# FPGA_BANK_B.net
KiCad netlist of a schematic drawn in Altium Designer
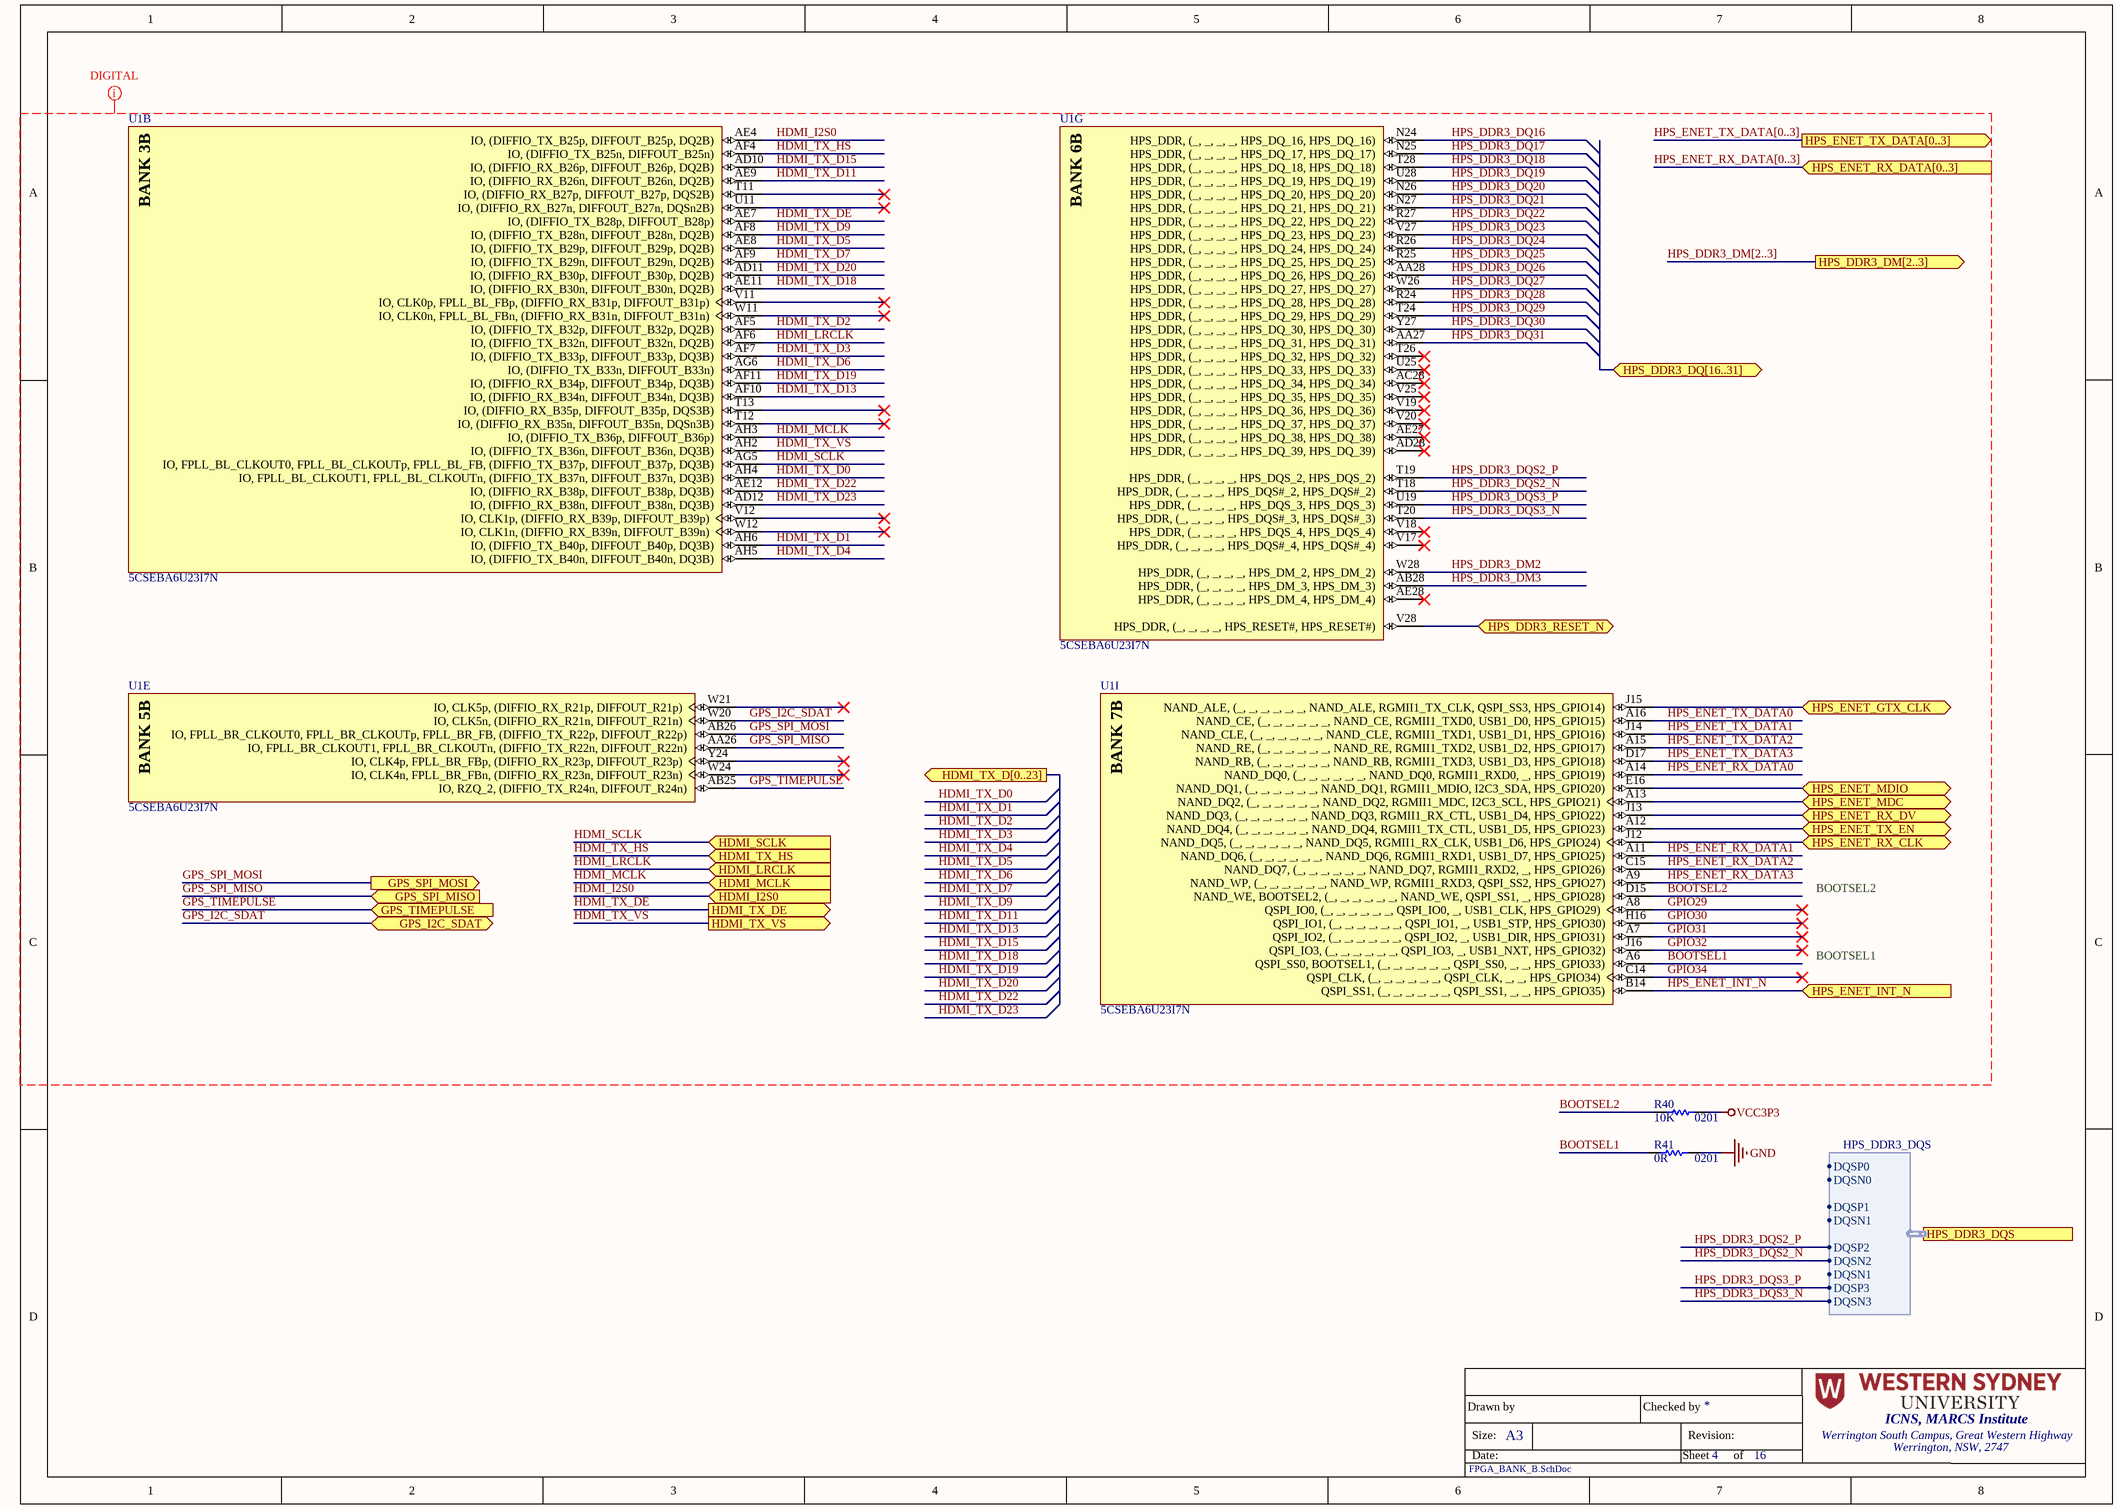
[diagram p0: FPGA_BANK_B.SchDoc]

(export (version "E")
  (design (tool "Eeschema 10.0.6"))
  (components
    (comp (ref "R40")
      (value "10K")
      (footprint "RES 0201 (0603)")
      (description "Res Thick Film 0201 10K Ohm 1% 0.05W(1/20W) ±200ppm/C Pad SMD Automotive T/R")
      (fields
        (field (name "MANUFACTURER") "Yageo")
        (field (name "MANUFACTURER PART NUMBER") "AC0201FR-0710KL")
        (field (name "CASE CODE (IMPERIAL)") "0201")
        (field (name "SOURCE") "ICNS_PropheseeLib.SchLib")
      )
      (libsource (lib "Western Sydney University - ICNS") (part "Symbol"))
    )
    (comp (ref "R41")
      (value "0R")
      (footprint "RES 0201 (0603)")
      (description "Res Thick Film 0201 0 Ohm Sulfur Resistant Pad SMD Automotive T/R")
      (fields
        (field (name "MANUFACTURER") "Yageo")
        (field (name "MANUFACTURER PART NUMBER") "AF0201JR-070RL")
        (field (name "CASE CODE (IMPERIAL)") "0201")
        (field (name "SOURCE") "ICNS_PropheseeLib.SchLib")
      )
      (libsource (lib "Western Sydney University - ICNS") (part "Symbol"))
    )
    (comp (ref "U1")
      (value "5CSEBA6U23I7N")
      (footprint "ALTR-UBGA672_A-185")
      (fields (field (name "MANUFACTURER") "Altera") (field (name "SOURCE") "ICNS_PropheseeLib.SchLib"))
      (libsource (lib "Western Sydney University - ICNS") (part "5CSEBA6U23I7N"))
    )
  )
  (nets
    (net (code "9") (name "/BOOTSEL1") (class "Default")
      (node (ref "R41") (pin "1") (pinfunction "1_1") (pintype "passive"))
      (node (ref "U1") (pin "A6") (pinfunction "QSPI_SS0,_BOOTSEL1,_(_,__,__,__,__,__,_QSPI_SS0,__,__,_HPS_GPIO33)_A6") (pintype "bidirectional"))
    )
    (net (code "10") (name "/BOOTSEL2") (class "Default")
      (node (ref "R40") (pin "2") (pinfunction "2_2") (pintype "passive"))
      (node (ref "U1") (pin "D15") (pinfunction "NAND_WE,_BOOTSEL2,_(_,__,__,__,__,__,_NAND_WE,_QSPI_SS1,__,_HPS_GPIO28)_D15") (pintype "bidirectional"))
    )
    (net (code "11") (name "/GPIO29") (class "Default")
      (node (ref "U1") (pin "A8") (pinfunction "QSPI_IO0,_(_,__,__,__,__,__,_QSPI_IO0,__,_USB1_CLK,_HPS_GPIO29)_A8") (pintype "bidirectional+no_connect"))
    )
    (net (code "12") (name "/GPIO30") (class "Default")
      (node (ref "U1") (pin "H16") (pinfunction "QSPI_IO1,_(_,__,__,__,__,__,_QSPI_IO1,__,_USB1_STP,_HPS_GPIO30)_H16") (pintype "bidirectional+no_connect"))
    )
    (net (code "13") (name "/GPIO31") (class "Default")
      (node (ref "U1") (pin "A7") (pinfunction "QSPI_IO2,_(_,__,__,__,__,__,_QSPI_IO2,__,_USB1_DIR,_HPS_GPIO31)_A7") (pintype "bidirectional+no_connect"))
    )
    (net (code "14") (name "/GPIO32") (class "Default")
      (node (ref "U1") (pin "J16") (pinfunction "QSPI_IO3,_(_,__,__,__,__,__,_QSPI_IO3,__,_USB1_NXT,_HPS_GPIO32)_J16") (pintype "bidirectional+no_connect"))
    )
    (net (code "15") (name "/GPIO34") (class "Default")
      (node (ref "U1") (pin "C14") (pinfunction "QSPI_CLK,_(_,__,__,__,__,__,_QSPI_CLK,__,__,_HPS_GPIO34)_C14") (pintype "bidirectional+no_connect"))
    )
    (net (code "16") (name "/GPS_I2C_SDAT") (class "Default")
      (node (ref "U1") (pin "W20") (pinfunction "IO,_CLK5n,_(DIFFIO_RX_R21n,_DIFFOUT_R21n)_W20") (pintype "bidirectional"))
    )
    (net (code "17") (name "/GPS_SPI_MISO") (class "Default")
      (node (ref "U1") (pin "AA26") (pinfunction "IO,_FPLL_BR_CLKOUT1,_FPLL_BR_CLKOUTn,_(DIFFIO_TX_R22n,_DIFFOUT_R22n)_AA26") (pintype "bidirectional"))
    )
    (net (code "18") (name "/GPS_SPI_MOSI") (class "Default")
      (node (ref "U1") (pin "AB26") (pinfunction "IO,_FPLL_BR_CLKOUT0,_FPLL_BR_CLKOUTp,_FPLL_BR_FB,_(DIFFIO_TX_R22p,_DIFFOUT_R22p)_AB26") (pintype "bidirectional"))
    )
    (net (code "19") (name "/GPS_TIMEPULSE") (class "Default")
      (node (ref "U1") (pin "AB25") (pinfunction "IO,_RZQ_2,_(DIFFIO_TX_R24n,_DIFFOUT_R24n)_AB25") (pintype "bidirectional"))
    )
    (net (code "20") (name "/HDMI_I2S0") (class "Default")
      (node (ref "U1") (pin "AE4") (pinfunction "IO,_(DIFFIO_TX_B25p,_DIFFOUT_B25p,_DQ2B)_AE4") (pintype "bidirectional"))
    )
    (net (code "21") (name "/HDMI_LRCLK") (class "Default")
      (node (ref "U1") (pin "AF6") (pinfunction "IO,_(DIFFIO_TX_B32n,_DIFFOUT_B32n,_DQ2B)_AF6") (pintype "bidirectional"))
    )
    (net (code "22") (name "/HDMI_MCLK") (class "Default")
      (node (ref "U1") (pin "AH3") (pinfunction "IO,_(DIFFIO_TX_B36p,_DIFFOUT_B36p)_AH3") (pintype "bidirectional"))
    )
    (net (code "23") (name "/HDMI_SCLK") (class "Default")
      (node (ref "U1") (pin "AG5") (pinfunction "IO,_FPLL_BL_CLKOUT0,_FPLL_BL_CLKOUTp,_FPLL_BL_FB,_(DIFFIO_TX_B37p,_DIFFOUT_B37p,_DQ3B)_AG5") (pintype "bidirectional"))
    )
    (net (code "24") (name "/HDMI_TX_D0") (class "Default")
      (node (ref "U1") (pin "AH4") (pinfunction "IO,_FPLL_BL_CLKOUT1,_FPLL_BL_CLKOUTn,_(DIFFIO_TX_B37n,_DIFFOUT_B37n,_DQ3B)_AH4") (pintype "bidirectional"))
    )
    (net (code "25") (name "/HDMI_TX_D1") (class "Default")
      (node (ref "U1") (pin "AH6") (pinfunction "IO,_(DIFFIO_TX_B40p,_DIFFOUT_B40p,_DQ3B)_AH6") (pintype "bidirectional"))
    )
    (net (code "26") (name "/HDMI_TX_D2") (class "Default")
      (node (ref "U1") (pin "AF5") (pinfunction "IO,_(DIFFIO_TX_B32p,_DIFFOUT_B32p,_DQ2B)_AF5") (pintype "bidirectional"))
    )
    (net (code "27") (name "/HDMI_TX_D3") (class "Default")
      (node (ref "U1") (pin "AF7") (pinfunction "IO,_(DIFFIO_TX_B33p,_DIFFOUT_B33p,_DQ3B)_AF7") (pintype "bidirectional"))
    )
    (net (code "28") (name "/HDMI_TX_D4") (class "Default")
      (node (ref "U1") (pin "AH5") (pinfunction "IO,_(DIFFIO_TX_B40n,_DIFFOUT_B40n,_DQ3B)_AH5") (pintype "bidirectional"))
    )
    (net (code "29") (name "/HDMI_TX_D5") (class "Default")
      (node (ref "U1") (pin "AE8") (pinfunction "IO,_(DIFFIO_TX_B29p,_DIFFOUT_B29p,_DQ2B)_AE8") (pintype "bidirectional"))
    )
    (net (code "30") (name "/HDMI_TX_D6") (class "Default")
      (node (ref "U1") (pin "AG6") (pinfunction "IO,_(DIFFIO_TX_B33n,_DIFFOUT_B33n)_AG6") (pintype "bidirectional"))
    )
    (net (code "31") (name "/HDMI_TX_D7") (class "Default")
      (node (ref "U1") (pin "AF9") (pinfunction "IO,_(DIFFIO_TX_B29n,_DIFFOUT_B29n,_DQ2B)_AF9") (pintype "bidirectional"))
    )
    (net (code "32") (name "/HDMI_TX_D9") (class "Default")
      (node (ref "U1") (pin "AF8") (pinfunction "IO,_(DIFFIO_TX_B28n,_DIFFOUT_B28n,_DQ2B)_AF8") (pintype "bidirectional"))
    )
    (net (code "33") (name "/HDMI_TX_D11") (class "Default")
      (node (ref "U1") (pin "AE9") (pinfunction "IO,_(DIFFIO_RX_B26n,_DIFFOUT_B26n,_DQ2B)_AE9") (pintype "bidirectional"))
    )
    (net (code "34") (name "/HDMI_TX_D13") (class "Default")
      (node (ref "U1") (pin "AF10") (pinfunction "IO,_(DIFFIO_RX_B34n,_DIFFOUT_B34n,_DQ3B)_AF10") (pintype "bidirectional"))
    )
    (net (code "35") (name "/HDMI_TX_D15") (class "Default")
      (node (ref "U1") (pin "AD10") (pinfunction "IO,_(DIFFIO_RX_B26p,_DIFFOUT_B26p,_DQ2B)_AD10") (pintype "bidirectional"))
    )
    (net (code "36") (name "/HDMI_TX_D18") (class "Default")
      (node (ref "U1") (pin "AE11") (pinfunction "IO,_(DIFFIO_RX_B30n,_DIFFOUT_B30n,_DQ2B)_AE11") (pintype "bidirectional"))
    )
    (net (code "37") (name "/HDMI_TX_D19") (class "Default")
      (node (ref "U1") (pin "AF11") (pinfunction "IO,_(DIFFIO_RX_B34p,_DIFFOUT_B34p,_DQ3B)_AF11") (pintype "bidirectional"))
    )
    (net (code "38") (name "/HDMI_TX_D20") (class "Default")
      (node (ref "U1") (pin "AD11") (pinfunction "IO,_(DIFFIO_RX_B30p,_DIFFOUT_B30p,_DQ2B)_AD11") (pintype "bidirectional"))
    )
    (net (code "39") (name "/HDMI_TX_D22") (class "Default")
      (node (ref "U1") (pin "AE12") (pinfunction "IO,_(DIFFIO_RX_B38p,_DIFFOUT_B38p,_DQ3B)_AE12") (pintype "bidirectional"))
    )
    (net (code "40") (name "/HDMI_TX_D23") (class "Default")
      (node (ref "U1") (pin "AD12") (pinfunction "IO,_(DIFFIO_RX_B38n,_DIFFOUT_B38n,_DQ3B)_AD12") (pintype "bidirectional"))
    )
    (net (code "41") (name "/HDMI_TX_DE") (class "Default")
      (node (ref "U1") (pin "AE7") (pinfunction "IO,_(DIFFIO_TX_B28p,_DIFFOUT_B28p)_AE7") (pintype "bidirectional"))
    )
    (net (code "43") (name "/HDMI_TX_HS") (class "Default")
      (node (ref "U1") (pin "AF4") (pinfunction "IO,_(DIFFIO_TX_B25n,_DIFFOUT_B25n)_AF4") (pintype "bidirectional"))
    )
    (net (code "44") (name "/HDMI_TX_VS") (class "Default")
      (node (ref "U1") (pin "AH2") (pinfunction "IO,_(DIFFIO_TX_B36n,_DIFFOUT_B36n,_DQ3B)_AH2") (pintype "bidirectional"))
    )
    (net (code "45") (name "/HPS_DDR3_DM2") (class "Default")
      (node (ref "U1") (pin "W28") (pinfunction "HPS_DDR,_(_,__,__,__,_HPS_DM_2,_HPS_DM_2)_W28") (pintype "bidirectional"))
    )
    (net (code "46") (name "/HPS_DDR3_DM3") (class "Default")
      (node (ref "U1") (pin "AB28") (pinfunction "HPS_DDR,_(_,__,__,__,_HPS_DM_3,_HPS_DM_3)_AB28") (pintype "bidirectional"))
    )
    (net (code "48") (name "/HPS_DDR3_DQ16") (class "Default")
      (node (ref "U1") (pin "N24") (pinfunction "HPS_DDR,_(_,__,__,__,_HPS_DQ_16,_HPS_DQ_16)_N24") (pintype "bidirectional"))
    )
    (net (code "49") (name "/HPS_DDR3_DQ17") (class "Default")
      (node (ref "U1") (pin "N25") (pinfunction "HPS_DDR,_(_,__,__,__,_HPS_DQ_17,_HPS_DQ_17)_N25") (pintype "bidirectional"))
    )
    (net (code "50") (name "/HPS_DDR3_DQ18") (class "Default")
      (node (ref "U1") (pin "T28") (pinfunction "HPS_DDR,_(_,__,__,__,_HPS_DQ_18,_HPS_DQ_18)_T28") (pintype "bidirectional"))
    )
    (net (code "51") (name "/HPS_DDR3_DQ19") (class "Default")
      (node (ref "U1") (pin "U28") (pinfunction "HPS_DDR,_(_,__,__,__,_HPS_DQ_19,_HPS_DQ_19)_U28") (pintype "bidirectional"))
    )
    (net (code "52") (name "/HPS_DDR3_DQ20") (class "Default")
      (node (ref "U1") (pin "N26") (pinfunction "HPS_DDR,_(_,__,__,__,_HPS_DQ_20,_HPS_DQ_20)_N26") (pintype "bidirectional"))
    )
    (net (code "53") (name "/HPS_DDR3_DQ21") (class "Default")
      (node (ref "U1") (pin "N27") (pinfunction "HPS_DDR,_(_,__,__,__,_HPS_DQ_21,_HPS_DQ_21)_N27") (pintype "bidirectional"))
    )
    (net (code "54") (name "/HPS_DDR3_DQ22") (class "Default")
      (node (ref "U1") (pin "R27") (pinfunction "HPS_DDR,_(_,__,__,__,_HPS_DQ_22,_HPS_DQ_22)_R27") (pintype "bidirectional"))
    )
    (net (code "55") (name "/HPS_DDR3_DQ23") (class "Default")
      (node (ref "U1") (pin "V27") (pinfunction "HPS_DDR,_(_,__,__,__,_HPS_DQ_23,_HPS_DQ_23)_V27") (pintype "bidirectional"))
    )
    (net (code "56") (name "/HPS_DDR3_DQ24") (class "Default")
      (node (ref "U1") (pin "R26") (pinfunction "HPS_DDR,_(_,__,__,__,_HPS_DQ_24,_HPS_DQ_24)_R26") (pintype "bidirectional"))
    )
    (net (code "57") (name "/HPS_DDR3_DQ25") (class "Default")
      (node (ref "U1") (pin "R25") (pinfunction "HPS_DDR,_(_,__,__,__,_HPS_DQ_25,_HPS_DQ_25)_R25") (pintype "bidirectional"))
    )
    (net (code "58") (name "/HPS_DDR3_DQ26") (class "Default")
      (node (ref "U1") (pin "AA28") (pinfunction "HPS_DDR,_(_,__,__,__,_HPS_DQ_26,_HPS_DQ_26)_AA28") (pintype "bidirectional"))
    )
    (net (code "59") (name "/HPS_DDR3_DQ27") (class "Default")
      (node (ref "U1") (pin "W26") (pinfunction "HPS_DDR,_(_,__,__,__,_HPS_DQ_27,_HPS_DQ_27)_W26") (pintype "bidirectional"))
    )
    (net (code "60") (name "/HPS_DDR3_DQ28") (class "Default")
      (node (ref "U1") (pin "R24") (pinfunction "HPS_DDR,_(_,__,__,__,_HPS_DQ_28,_HPS_DQ_28)_R24") (pintype "bidirectional"))
    )
    (net (code "61") (name "/HPS_DDR3_DQ29") (class "Default")
      (node (ref "U1") (pin "T24") (pinfunction "HPS_DDR,_(_,__,__,__,_HPS_DQ_29,_HPS_DQ_29)_T24") (pintype "bidirectional"))
    )
    (net (code "62") (name "/HPS_DDR3_DQ30") (class "Default")
      (node (ref "U1") (pin "Y27") (pinfunction "HPS_DDR,_(_,__,__,__,_HPS_DQ_30,_HPS_DQ_30)_Y27") (pintype "bidirectional"))
    )
    (net (code "63") (name "/HPS_DDR3_DQ31") (class "Default")
      (node (ref "U1") (pin "AA27") (pinfunction "HPS_DDR,_(_,__,__,__,_HPS_DQ_31,_HPS_DQ_31)_AA27") (pintype "bidirectional"))
    )
    (net (code "64") (name "/HPS_DDR3_DQS2_N") (class "Default")
      (node (ref "U1") (pin "T18") (pinfunction "HPS_DDR,_(_,__,__,__,_HPS_DQS#_2,_HPS_DQS#_2)_T18") (pintype "bidirectional"))
    )
    (net (code "65") (name "/HPS_DDR3_DQS2_P") (class "Default")
      (node (ref "U1") (pin "T19") (pinfunction "HPS_DDR,_(_,__,__,__,_HPS_DQS_2,_HPS_DQS_2)_T19") (pintype "bidirectional"))
    )
    (net (code "66") (name "/HPS_DDR3_DQS3_N") (class "Default")
      (node (ref "U1") (pin "T20") (pinfunction "HPS_DDR,_(_,__,__,__,_HPS_DQS#_3,_HPS_DQS#_3)_T20") (pintype "bidirectional"))
    )
    (net (code "67") (name "/HPS_DDR3_DQS3_P") (class "Default")
      (node (ref "U1") (pin "U19") (pinfunction "HPS_DDR,_(_,__,__,__,_HPS_DQS_3,_HPS_DQS_3)_U19") (pintype "bidirectional"))
    )
    (net (code "69") (name "/HPS_DDR3_RESET_N") (class "Default")
      (node (ref "U1") (pin "V28") (pinfunction "HPS_DDR,_(_,__,__,__,_HPS_RESET#,_HPS_RESET#)_V28") (pintype "bidirectional"))
    )
    (net (code "70") (name "/HPS_ENET_GTX_CLK") (class "Default")
      (node (ref "U1") (pin "J15") (pinfunction "NAND_ALE,_(_,__,__,__,__,__,_NAND_ALE,_RGMII1_TX_CLK,_QSPI_SS3,_HPS_GPIO14)_J15") (pintype "bidirectional"))
    )
    (net (code "71") (name "/HPS_ENET_INT_N") (class "Default")
      (node (ref "U1") (pin "B14") (pinfunction "QSPI_SS1,_(_,__,__,__,__,__,_QSPI_SS1,__,__,_HPS_GPIO35)_B14") (pintype "bidirectional"))
    )
    (net (code "72") (name "/HPS_ENET_MDC") (class "Default")
      (node (ref "U1") (pin "A13") (pinfunction "NAND_DQ2,_(_,__,__,__,__,__,_NAND_DQ2,_RGMII1_MDC,_I2C3_SCL,_HPS_GPIO21)_A13") (pintype "bidirectional"))
    )
    (net (code "73") (name "/HPS_ENET_MDIO") (class "Default")
      (node (ref "U1") (pin "E16") (pinfunction "NAND_DQ1,_(_,__,__,__,__,__,_NAND_DQ1,_RGMII1_MDIO,_I2C3_SDA,_HPS_GPIO20)_E16") (pintype "bidirectional"))
    )
    (net (code "74") (name "/HPS_ENET_RX_CLK") (class "Default")
      (node (ref "U1") (pin "J12") (pinfunction "NAND_DQ5,_(_,__,__,__,__,__,_NAND_DQ5,_RGMII1_RX_CLK,_USB1_D6,_HPS_GPIO24)_J12") (pintype "bidirectional"))
    )
    (net (code "75") (name "/HPS_ENET_RX_DATA0") (class "Default")
      (node (ref "U1") (pin "A14") (pinfunction "NAND_DQ0,_(_,__,__,__,__,__,_NAND_DQ0,_RGMII1_RXD0,__,_HPS_GPIO19)_A14") (pintype "bidirectional"))
    )
    (net (code "76") (name "/HPS_ENET_RX_DATA1") (class "Default")
      (node (ref "U1") (pin "A11") (pinfunction "NAND_DQ6,_(_,__,__,__,__,__,_NAND_DQ6,_RGMII1_RXD1,_USB1_D7,_HPS_GPIO25)_A11") (pintype "bidirectional"))
    )
    (net (code "77") (name "/HPS_ENET_RX_DATA2") (class "Default")
      (node (ref "U1") (pin "C15") (pinfunction "NAND_DQ7,_(_,__,__,__,__,__,_NAND_DQ7,_RGMII1_RXD2,__,_HPS_GPIO26)_C15") (pintype "bidirectional"))
    )
    (net (code "78") (name "/HPS_ENET_RX_DATA3") (class "Default")
      (node (ref "U1") (pin "A9") (pinfunction "NAND_WP,_(_,__,__,__,__,__,_NAND_WP,_RGMII1_RXD3,_QSPI_SS2,_HPS_GPIO27)_A9") (pintype "bidirectional"))
    )
    (net (code "80") (name "/HPS_ENET_RX_DV") (class "Default")
      (node (ref "U1") (pin "J13") (pinfunction "NAND_DQ3,_(_,__,__,__,__,__,_NAND_DQ3,_RGMII1_RX_CTL,_USB1_D4,_HPS_GPIO22)_J13") (pintype "bidirectional"))
    )
    (net (code "81") (name "/HPS_ENET_TX_DATA0") (class "Default")
      (node (ref "U1") (pin "A16") (pinfunction "NAND_CE,_(_,__,__,__,__,__,_NAND_CE,_RGMII1_TXD0,_USB1_D0,_HPS_GPIO15)_A16") (pintype "bidirectional"))
    )
    (net (code "82") (name "/HPS_ENET_TX_DATA1") (class "Default")
      (node (ref "U1") (pin "J14") (pinfunction "NAND_CLE,_(_,__,__,__,__,__,_NAND_CLE,_RGMII1_TXD1,_USB1_D1,_HPS_GPIO16)_J14") (pintype "bidirectional"))
    )
    (net (code "83") (name "/HPS_ENET_TX_DATA2") (class "Default")
      (node (ref "U1") (pin "A15") (pinfunction "NAND_RE,_(_,__,__,__,__,__,_NAND_RE,_RGMII1_TXD2,_USB1_D2,_HPS_GPIO17)_A15") (pintype "bidirectional"))
    )
    (net (code "84") (name "/HPS_ENET_TX_DATA3") (class "Default")
      (node (ref "U1") (pin "D17") (pinfunction "NAND_RB,_(_,__,__,__,__,__,_NAND_RB,_RGMII1_TXD3,_USB1_D3,_HPS_GPIO18)_D17") (pintype "bidirectional"))
    )
    (net (code "86") (name "/HPS_ENET_TX_EN") (class "Default")
      (node (ref "U1") (pin "A12") (pinfunction "NAND_DQ4,_(_,__,__,__,__,__,_NAND_DQ4,_RGMII1_TX_CTL,_USB1_D5,_HPS_GPIO23)_A12") (pintype "bidirectional"))
    )
    (net (code "88") (name "GND") (class "Default")
      (node (ref "R41") (pin "2") (pinfunction "2_2") (pintype "passive"))
    )
    (net (code "89") (name "VCC3P3") (class "Default")
      (node (ref "R40") (pin "1") (pinfunction "1_1") (pintype "passive"))
    )
    (net (code "90") (name "unconnected-(U1B-IO,_(DIFFIO_RX_B27n,_DIFFOUT_B27n,_DQSn2B)-PadU11)") (class "Default")
      (node (ref "U1") (pin "U11") (pinfunction "IO,_(DIFFIO_RX_B27n,_DIFFOUT_B27n,_DQSn2B)_U11") (pintype "bidirectional+no_connect"))
    )
    (net (code "91") (name "unconnected-(U1B-IO,_(DIFFIO_RX_B27p,_DIFFOUT_B27p,_DQS2B)-PadT11)") (class "Default")
      (node (ref "U1") (pin "T11") (pinfunction "IO,_(DIFFIO_RX_B27p,_DIFFOUT_B27p,_DQS2B)_T11") (pintype "bidirectional+no_connect"))
    )
    (net (code "92") (name "unconnected-(U1B-IO,_(DIFFIO_RX_B35n,_DIFFOUT_B35n,_DQSn3B)-PadT12)") (class "Default")
      (node (ref "U1") (pin "T12") (pinfunction "IO,_(DIFFIO_RX_B35n,_DIFFOUT_B35n,_DQSn3B)_T12") (pintype "bidirectional+no_connect"))
    )
    (net (code "93") (name "unconnected-(U1B-IO,_(DIFFIO_RX_B35p,_DIFFOUT_B35p,_DQS3B)-PadT13)") (class "Default")
      (node (ref "U1") (pin "T13") (pinfunction "IO,_(DIFFIO_RX_B35p,_DIFFOUT_B35p,_DQS3B)_T13") (pintype "bidirectional+no_connect"))
    )
    (net (code "94") (name "unconnected-(U1B-IO,_CLK0n,_FPLL_BL_FBn,_(DIFFIO_RX_B31n,_DIFFOUT_B31n)-PadW11)") (class "Default")
      (node (ref "U1") (pin "W11") (pinfunction "IO,_CLK0n,_FPLL_BL_FBn,_(DIFFIO_RX_B31n,_DIFFOUT_B31n)_W11") (pintype "bidirectional+no_connect"))
    )
    (net (code "95") (name "unconnected-(U1B-IO,_CLK0p,_FPLL_BL_FBp,_(DIFFIO_RX_B31p,_DIFFOUT_B31p)-PadV11)") (class "Default")
      (node (ref "U1") (pin "V11") (pinfunction "IO,_CLK0p,_FPLL_BL_FBp,_(DIFFIO_RX_B31p,_DIFFOUT_B31p)_V11") (pintype "bidirectional+no_connect"))
    )
    (net (code "96") (name "unconnected-(U1B-IO,_CLK1n,_(DIFFIO_RX_B39n,_DIFFOUT_B39n)-PadW12)") (class "Default")
      (node (ref "U1") (pin "W12") (pinfunction "IO,_CLK1n,_(DIFFIO_RX_B39n,_DIFFOUT_B39n)_W12") (pintype "bidirectional+no_connect"))
    )
    (net (code "97") (name "unconnected-(U1B-IO,_CLK1p,_(DIFFIO_RX_B39p,_DIFFOUT_B39p)-PadV12)") (class "Default")
      (node (ref "U1") (pin "V12") (pinfunction "IO,_CLK1p,_(DIFFIO_RX_B39p,_DIFFOUT_B39p)_V12") (pintype "bidirectional+no_connect"))
    )
    (net (code "98") (name "unconnected-(U1E-IO,_CLK4n,_FPLL_BR_FBn,_(DIFFIO_RX_R23n,_DIFFOUT_R23n)-PadW24)") (class "Default")
      (node (ref "U1") (pin "W24") (pinfunction "IO,_CLK4n,_FPLL_BR_FBn,_(DIFFIO_RX_R23n,_DIFFOUT_R23n)_W24") (pintype "bidirectional+no_connect"))
    )
    (net (code "99") (name "unconnected-(U1E-IO,_CLK4p,_FPLL_BR_FBp,_(DIFFIO_RX_R23p,_DIFFOUT_R23p)-PadY24)") (class "Default")
      (node (ref "U1") (pin "Y24") (pinfunction "IO,_CLK4p,_FPLL_BR_FBp,_(DIFFIO_RX_R23p,_DIFFOUT_R23p)_Y24") (pintype "bidirectional+no_connect"))
    )
    (net (code "100") (name "unconnected-(U1E-IO,_CLK5p,_(DIFFIO_RX_R21p,_DIFFOUT_R21p)-PadW21)") (class "Default")
      (node (ref "U1") (pin "W21") (pinfunction "IO,_CLK5p,_(DIFFIO_RX_R21p,_DIFFOUT_R21p)_W21") (pintype "bidirectional+no_connect"))
    )
    (net (code "101") (name "unconnected-(U1G-HPS_DDR,_(_,__,__,__,_HPS_DM_4,_HPS_DM_4)-PadAE28)") (class "Default")
      (node (ref "U1") (pin "AE28") (pinfunction "HPS_DDR,_(_,__,__,__,_HPS_DM_4,_HPS_DM_4)_AE28") (pintype "bidirectional+no_connect"))
    )
    (net (code "102") (name "unconnected-(U1G-HPS_DDR,_(_,__,__,__,_HPS_DQS#_4,_HPS_DQS#_4)-PadV17)") (class "Default")
      (node (ref "U1") (pin "V17") (pinfunction "HPS_DDR,_(_,__,__,__,_HPS_DQS#_4,_HPS_DQS#_4)_V17") (pintype "bidirectional+no_connect"))
    )
    (net (code "103") (name "unconnected-(U1G-HPS_DDR,_(_,__,__,__,_HPS_DQS_4,_HPS_DQS_4)-PadV18)") (class "Default")
      (node (ref "U1") (pin "V18") (pinfunction "HPS_DDR,_(_,__,__,__,_HPS_DQS_4,_HPS_DQS_4)_V18") (pintype "bidirectional+no_connect"))
    )
    (net (code "104") (name "unconnected-(U1G-HPS_DDR,_(_,__,__,__,_HPS_DQ_32,_HPS_DQ_32)-PadT26)") (class "Default")
      (node (ref "U1") (pin "T26") (pinfunction "HPS_DDR,_(_,__,__,__,_HPS_DQ_32,_HPS_DQ_32)_T26") (pintype "bidirectional+no_connect"))
    )
    (net (code "105") (name "unconnected-(U1G-HPS_DDR,_(_,__,__,__,_HPS_DQ_33,_HPS_DQ_33)-PadU25)") (class "Default")
      (node (ref "U1") (pin "U25") (pinfunction "HPS_DDR,_(_,__,__,__,_HPS_DQ_33,_HPS_DQ_33)_U25") (pintype "bidirectional+no_connect"))
    )
    (net (code "106") (name "unconnected-(U1G-HPS_DDR,_(_,__,__,__,_HPS_DQ_34,_HPS_DQ_34)-PadAC28)") (class "Default")
      (node (ref "U1") (pin "AC28") (pinfunction "HPS_DDR,_(_,__,__,__,_HPS_DQ_34,_HPS_DQ_34)_AC28") (pintype "bidirectional+no_connect"))
    )
    (net (code "107") (name "unconnected-(U1G-HPS_DDR,_(_,__,__,__,_HPS_DQ_35,_HPS_DQ_35)-PadV25)") (class "Default")
      (node (ref "U1") (pin "V25") (pinfunction "HPS_DDR,_(_,__,__,__,_HPS_DQ_35,_HPS_DQ_35)_V25") (pintype "bidirectional+no_connect"))
    )
    (net (code "108") (name "unconnected-(U1G-HPS_DDR,_(_,__,__,__,_HPS_DQ_36,_HPS_DQ_36)-PadV19)") (class "Default")
      (node (ref "U1") (pin "V19") (pinfunction "HPS_DDR,_(_,__,__,__,_HPS_DQ_36,_HPS_DQ_36)_V19") (pintype "bidirectional+no_connect"))
    )
    (net (code "109") (name "unconnected-(U1G-HPS_DDR,_(_,__,__,__,_HPS_DQ_37,_HPS_DQ_37)-PadV20)") (class "Default")
      (node (ref "U1") (pin "V20") (pinfunction "HPS_DDR,_(_,__,__,__,_HPS_DQ_37,_HPS_DQ_37)_V20") (pintype "bidirectional+no_connect"))
    )
    (net (code "110") (name "unconnected-(U1G-HPS_DDR,_(_,__,__,__,_HPS_DQ_38,_HPS_DQ_38)-PadAE27)") (class "Default")
      (node (ref "U1") (pin "AE27") (pinfunction "HPS_DDR,_(_,__,__,__,_HPS_DQ_38,_HPS_DQ_38)_AE27") (pintype "bidirectional+no_connect"))
    )
    (net (code "111") (name "unconnected-(U1G-HPS_DDR,_(_,__,__,__,_HPS_DQ_39,_HPS_DQ_39)-PadAD28)") (class "Default")
      (node (ref "U1") (pin "AD28") (pinfunction "HPS_DDR,_(_,__,__,__,_HPS_DQ_39,_HPS_DQ_39)_AD28") (pintype "bidirectional+no_connect"))
    )
  )
)
